# Velvet_Controller.net
KiCad netlist of a schematic drawn in Altium Designer
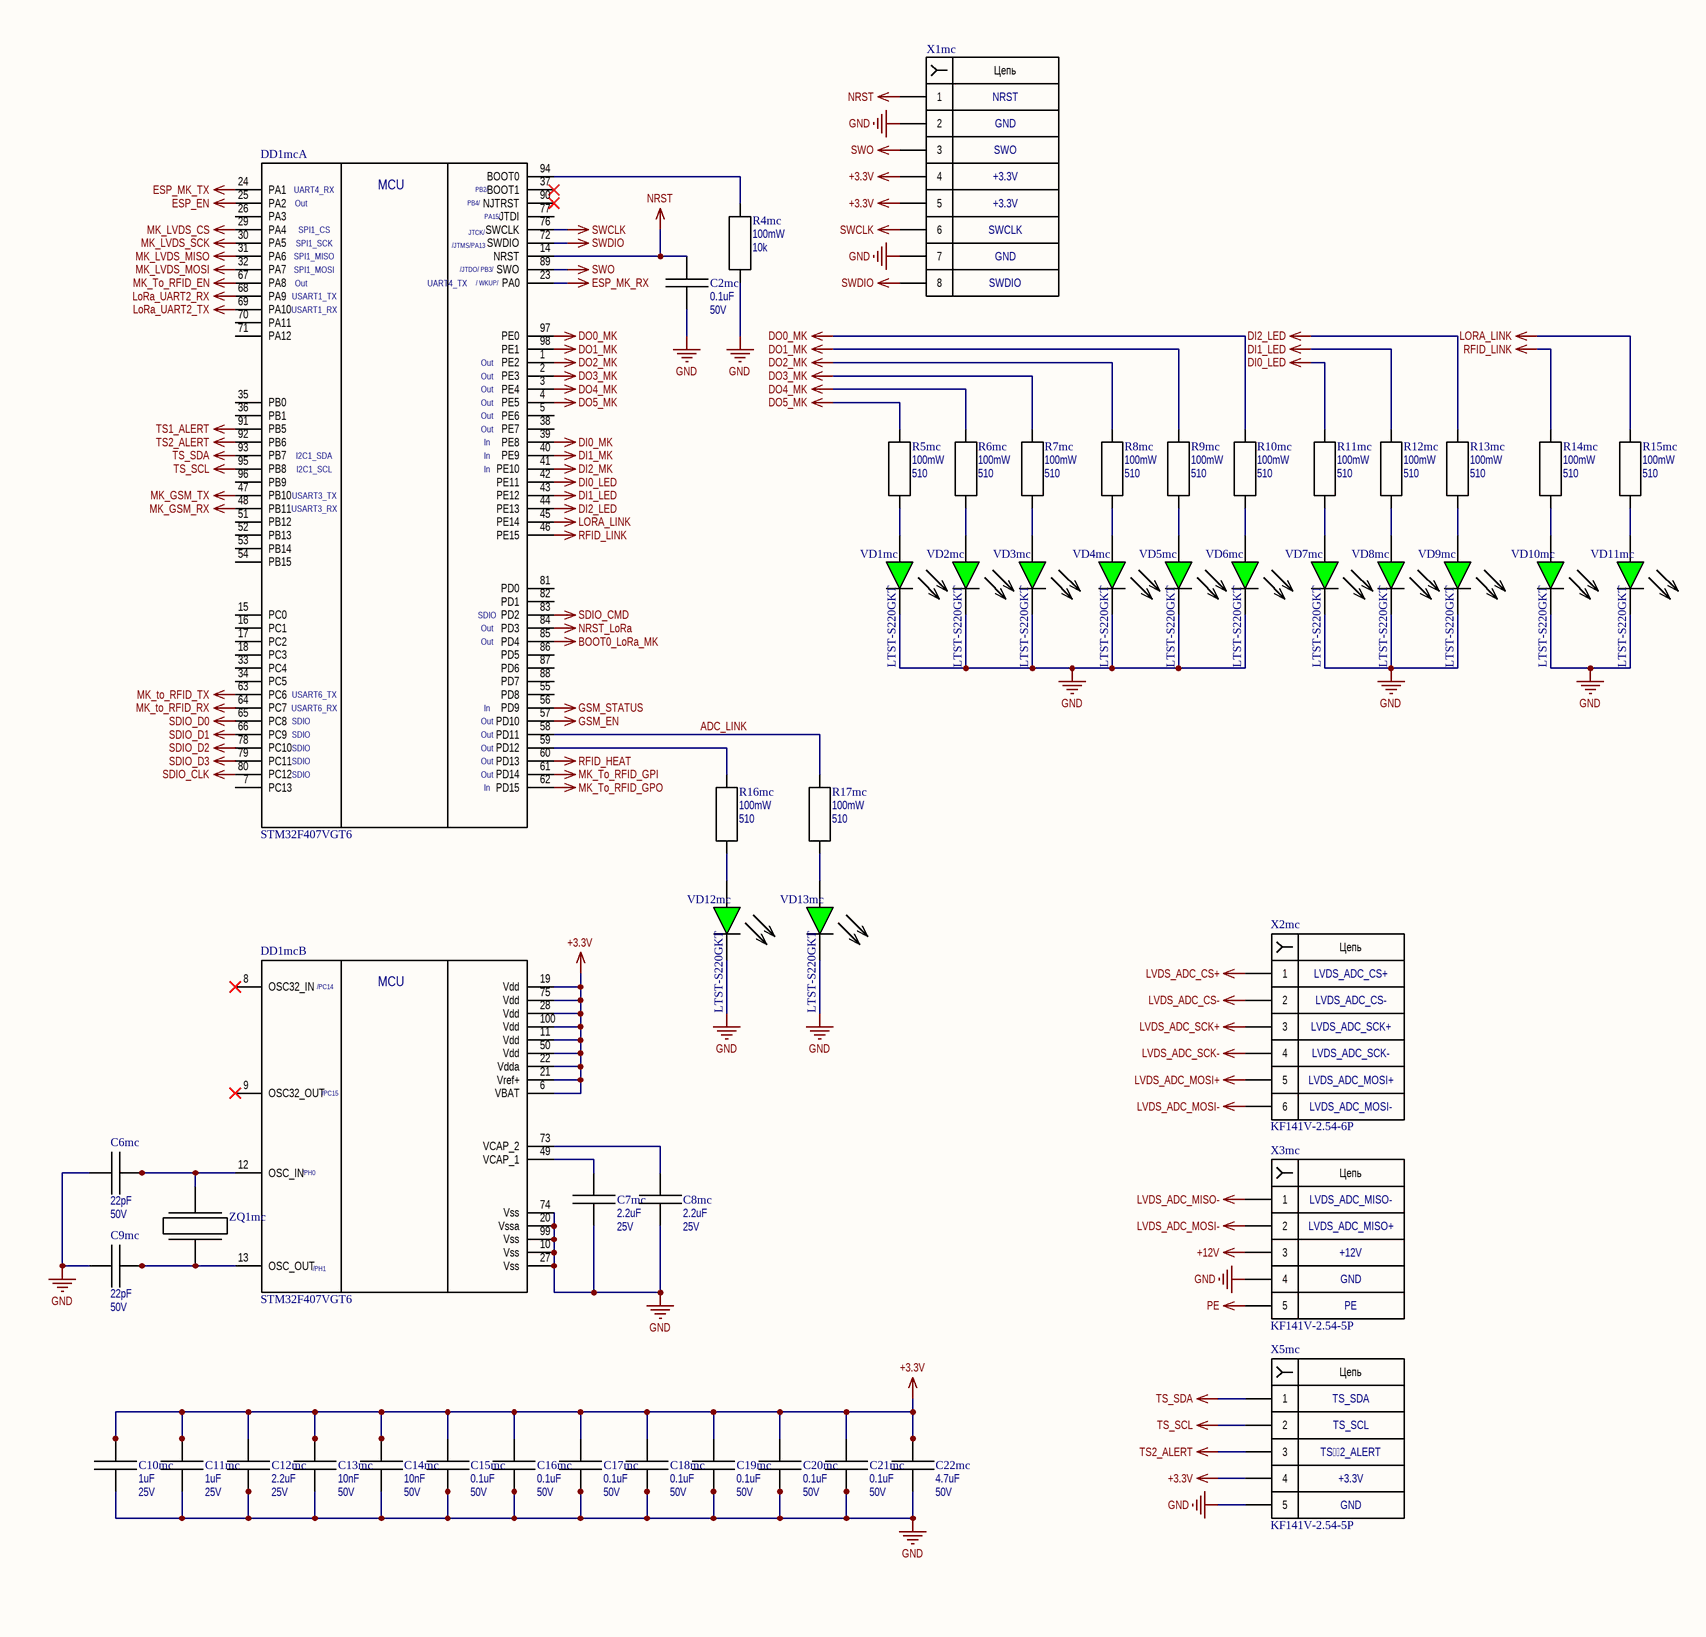
[diagram p0: Схема МК и датчиков Velvet Controller.SchDoc, left]
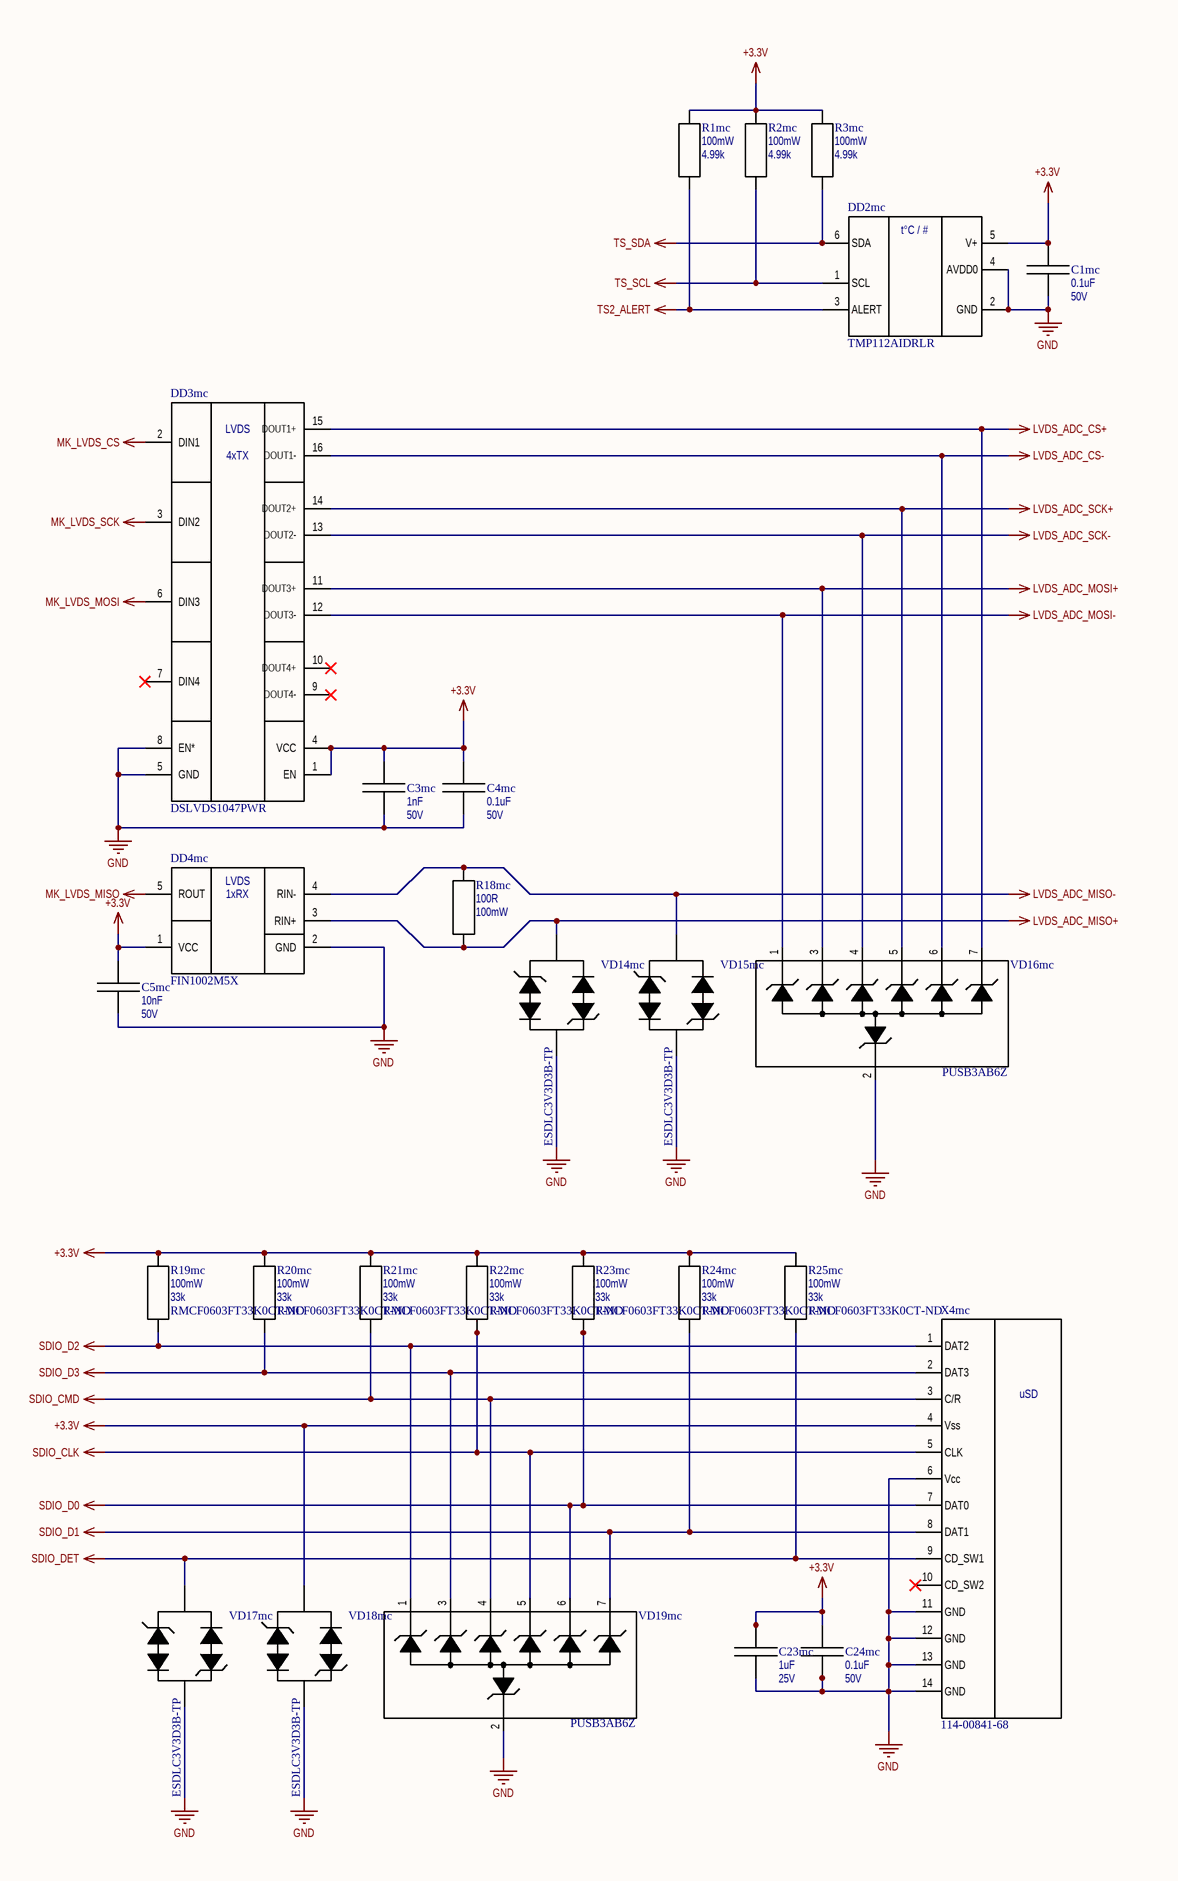
[diagram p1: Схема МК и датчиков Velvet Controller.SchDoc, right]

(export (version "E")
  (design (tool "Eeschema 10.0.6"))
  (components
    (comp (ref "C1mc")
      (value "GCM188R71H104KA57D")
      (footprint "CAP 0603 IPC MAX")
      (description "CAP SMD CER 0.1UF 50V X7R 0603")
      (fields
        (field (name "TOLERANCE") "10%")
        (field (name "CAPACITANCE") "0.1uF")
        (field (name "RATED VOLTAGE") "50V")
      )
      (libsource (lib "Passive components") (part "GCM188R71H104KA57D"))
    )
    (comp (ref "C2mc")
      (value "GCM188R71H104KA57D")
      (footprint "CAP 0603 IPC MAX")
      (description "CAP SMD CER 0.1UF 50V X7R 0603")
      (fields
        (field (name "TOLERANCE") "10%")
        (field (name "CAPACITANCE") "0.1uF")
        (field (name "RATED VOLTAGE") "50V")
      )
      (libsource (lib "Passive components") (part "GCM188R71H104KA57D"))
    )
    (comp (ref "C3mc")
      (value "GCM188R71H102KA37D")
      (footprint "CAP 0603 IPC MAX")
      (description "CAP SMD CER 1000PF 50V X7R 0603")
      (fields
        (field (name "TOLERANCE") "10%")
        (field (name "CAPACITANCE") "1nF")
        (field (name "RATED VOLTAGE") "50V")
      )
      (libsource (lib "Passive components") (part "GCM188R71H102KA37D"))
    )
    (comp (ref "C4mc")
      (value "GCM188R71H104KA57D")
      (footprint "CAP 0603 IPC MAX")
      (description "CAP SMD CER 0.1UF 50V X7R 0603")
      (fields
        (field (name "TOLERANCE") "10%")
        (field (name "CAPACITANCE") "0.1uF")
        (field (name "RATED VOLTAGE") "50V")
      )
      (libsource (lib "Passive components") (part "GCM188R71H104KA57D"))
    )
    (comp (ref "C5mc")
      (value "CL10B103KB8NNNC")
      (footprint "CAP 0603 IPC MAX")
      (description "CAP SMD CER 10000PF 50V X7R 0603")
      (fields
        (field (name "TOLERANCE") "10%")
        (field (name "CAPACITANCE") "10nF")
        (field (name "RATED VOLTAGE") "50V")
      )
      (libsource (lib "Passive components") (part "CL10B103KB8NNNC"))
    )
    (comp (ref "C6mc")
      (value "CC0603JRNPO9BN220")
      (footprint "CAP 0603 IPC MAX")
      (description "CAP SMD CER 22PF 50V NP0  0603")
      (fields
        (field (name "TOLERANCE") "5%")
        (field (name "CAPACITANCE") "22pF")
        (field (name "RATED VOLTAGE") "50V")
      )
      (libsource (lib "Passive components") (part "CC0603JRNPO9BN220"))
    )
    (comp (ref "C7mc")
      (value "GRM188R61E225KA12D")
      (footprint "CAP 0603 IPC MAX")
      (description "CAP SMD CER 2.2UF 25V X5R 0603")
      (fields
        (field (name "TOLERANCE") "10%")
        (field (name "CAPACITANCE") "2.2uF")
        (field (name "RATED VOLTAGE") "25V")
      )
      (libsource (lib "Passive components") (part "GRM188R61E225KA12D"))
    )
    (comp (ref "C8mc")
      (value "GRM188R61E225KA12D")
      (footprint "CAP 0603 IPC MAX")
      (description "CAP SMD CER 2.2UF 25V X5R 0603")
      (fields
        (field (name "TOLERANCE") "10%")
        (field (name "CAPACITANCE") "2.2uF")
        (field (name "RATED VOLTAGE") "25V")
      )
      (libsource (lib "Passive components") (part "GRM188R61E225KA12D"))
    )
    (comp (ref "C9mc")
      (value "CC0603JRNPO9BN220")
      (footprint "CAP 0603 IPC MAX")
      (description "CAP SMD CER 22PF 50V NP0  0603")
      (fields
        (field (name "TOLERANCE") "5%")
        (field (name "CAPACITANCE") "22pF")
        (field (name "RATED VOLTAGE") "50V")
      )
      (libsource (lib "Passive components") (part "CC0603JRNPO9BN220"))
    )
    (comp (ref "C10mc")
      (value "TMK107BJ105KA-T")
      (footprint "CAP 0603 IPC MAX")
      (description "CAP SMD CER 1UF 25V X5R 0603")
      (fields
        (field (name "TOLERANCE") "10%")
        (field (name "CAPACITANCE") "1uF")
        (field (name "RATED VOLTAGE") "25V")
      )
      (libsource (lib "Passive components") (part "TMK107BJ105KA-T"))
    )
    (comp (ref "C11mc")
      (value "TMK107BJ105KA-T")
      (footprint "CAP 0603 IPC MAX")
      (description "CAP SMD CER 1UF 25V X5R 0603")
      (fields
        (field (name "TOLERANCE") "10%")
        (field (name "CAPACITANCE") "1uF")
        (field (name "RATED VOLTAGE") "25V")
      )
      (libsource (lib "Passive components") (part "TMK107BJ105KA-T"))
    )
    (comp (ref "C12mc")
      (value "GRM188R61E225KA12D")
      (footprint "CAP 0603 IPC MAX")
      (description "CAP SMD CER 2.2UF 25V X5R 0603")
      (fields
        (field (name "TOLERANCE") "10%")
        (field (name "CAPACITANCE") "2.2uF")
        (field (name "RATED VOLTAGE") "25V")
      )
      (libsource (lib "Passive components") (part "GRM188R61E225KA12D"))
    )
    (comp (ref "C13mc")
      (value "CL10B103KB8NNNC")
      (footprint "CAP 0603 IPC MAX")
      (description "CAP SMD CER 10000PF 50V X7R 0603")
      (fields
        (field (name "TOLERANCE") "10%")
        (field (name "CAPACITANCE") "10nF")
        (field (name "RATED VOLTAGE") "50V")
      )
      (libsource (lib "Passive components") (part "CL10B103KB8NNNC"))
    )
    (comp (ref "C14mc")
      (value "CL10B103KB8NNNC")
      (footprint "CAP 0603 IPC MAX")
      (description "CAP SMD CER 10000PF 50V X7R 0603")
      (fields
        (field (name "TOLERANCE") "10%")
        (field (name "CAPACITANCE") "10nF")
        (field (name "RATED VOLTAGE") "50V")
      )
      (libsource (lib "Passive components") (part "CL10B103KB8NNNC"))
    )
    (comp (ref "C15mc")
      (value "GCM188R71H104KA57D")
      (footprint "CAP 0603 IPC MAX")
      (description "CAP SMD CER 0.1UF 50V X7R 0603")
      (fields
        (field (name "TOLERANCE") "10%")
        (field (name "CAPACITANCE") "0.1uF")
        (field (name "RATED VOLTAGE") "50V")
      )
      (libsource (lib "Passive components") (part "GCM188R71H104KA57D"))
    )
    (comp (ref "C16mc")
      (value "GCM188R71H104KA57D")
      (footprint "CAP 0603 IPC MAX")
      (description "CAP SMD CER 0.1UF 50V X7R 0603")
      (fields
        (field (name "TOLERANCE") "10%")
        (field (name "CAPACITANCE") "0.1uF")
        (field (name "RATED VOLTAGE") "50V")
      )
      (libsource (lib "Passive components") (part "GCM188R71H104KA57D"))
    )
    (comp (ref "C17mc")
      (value "GCM188R71H104KA57D")
      (footprint "CAP 0603 IPC MAX")
      (description "CAP SMD CER 0.1UF 50V X7R 0603")
      (fields
        (field (name "TOLERANCE") "10%")
        (field (name "CAPACITANCE") "0.1uF")
        (field (name "RATED VOLTAGE") "50V")
      )
      (libsource (lib "Passive components") (part "GCM188R71H104KA57D"))
    )
    (comp (ref "C18mc")
      (value "GCM188R71H104KA57D")
      (footprint "CAP 0603 IPC MAX")
      (description "CAP SMD CER 0.1UF 50V X7R 0603")
      (fields
        (field (name "TOLERANCE") "10%")
        (field (name "CAPACITANCE") "0.1uF")
        (field (name "RATED VOLTAGE") "50V")
      )
      (libsource (lib "Passive components") (part "GCM188R71H104KA57D"))
    )
    (comp (ref "C19mc")
      (value "GCM188R71H104KA57D")
      (footprint "CAP 0603 IPC MAX")
      (description "CAP SMD CER 0.1UF 50V X7R 0603")
      (fields
        (field (name "TOLERANCE") "10%")
        (field (name "CAPACITANCE") "0.1uF")
        (field (name "RATED VOLTAGE") "50V")
      )
      (libsource (lib "Passive components") (part "GCM188R71H104KA57D"))
    )
    (comp (ref "C20mc")
      (value "GCM188R71H104KA57D")
      (footprint "CAP 0603 IPC MAX")
      (description "CAP SMD CER 0.1UF 50V X7R 0603")
      (fields
        (field (name "TOLERANCE") "10%")
        (field (name "CAPACITANCE") "0.1uF")
        (field (name "RATED VOLTAGE") "50V")
      )
      (libsource (lib "Passive components") (part "GCM188R71H104KA57D"))
    )
    (comp (ref "C21mc")
      (value "GCM188R71H104KA57D")
      (footprint "CAP 0603 IPC MAX")
      (description "CAP SMD CER 0.1UF 50V X7R 0603")
      (fields
        (field (name "TOLERANCE") "10%")
        (field (name "CAPACITANCE") "0.1uF")
        (field (name "RATED VOLTAGE") "50V")
      )
      (libsource (lib "Passive components") (part "GCM188R71H104KA57D"))
    )
    (comp (ref "C22mc")
      (value "CL21A475KBQNNNE")
      (footprint "CAP 0805 IPC MAX")
      (description "CAP SMD CER 4.7UF 50V X5R 0805")
      (fields
        (field (name "TOLERANCE") "10%")
        (field (name "CAPACITANCE") "4.7uF")
        (field (name "RATED VOLTAGE") "50V")
      )
      (libsource (lib "Passive components") (part "CL21A475KBQNNNE"))
    )
    (comp (ref "C23mc")
      (value "TMK107BJ105KA-T")
      (footprint "CAP 0603 IPC MAX")
      (description "CAP SMD CER 1UF 25V X5R 0603")
      (fields
        (field (name "TOLERANCE") "10%")
        (field (name "CAPACITANCE") "1uF")
        (field (name "RATED VOLTAGE") "25V")
      )
      (libsource (lib "Passive components") (part "TMK107BJ105KA-T"))
    )
    (comp (ref "C24mc")
      (value "GCM188R71H104KA57D")
      (footprint "CAP 0603 IPC MAX")
      (description "CAP SMD CER 0.1UF 50V X7R 0603")
      (fields
        (field (name "TOLERANCE") "10%")
        (field (name "CAPACITANCE") "0.1uF")
        (field (name "RATED VOLTAGE") "50V")
      )
      (libsource (lib "Passive components") (part "GCM188R71H104KA57D"))
    )
    (comp (ref "DD1mc")
      (value "STM32F407VGT6")
      (footprint "LQFP50P1600X1600X160-100M")
      (description "IC MCU 32BIT 1MB FLASH 100LQFP")
      (libsource (lib "Digital") (part "STM32F407VGT6"))
    )
    (comp (ref "DD2mc")
      (value "TMP112AIDRLR")
      (footprint "SOT-563")
      (description "SOT-563 TEMPERATURE SENSORS ROHS")
      (libsource (lib "Digital") (part "TMP112AIDRLR"))
    )
    (comp (ref "DD3mc")
      (value "DSLVDS1047PWR")
      (footprint "TSSOP-16")
      (description "IC DRIVER LVDS FULL 4/0 16TSSOP")
      (libsource (lib "Digital") (part "DSLVDS1047PWR"))
    )
    (comp (ref "DD4mc")
      (value "FIN1002M5X")
      (footprint "SOT-23-5")
      (description "IC RECEIVER LVDS 0/1 SOT23-5")
      (libsource (lib "Digital") (part "FIN1002M5X"))
    )
    (comp (ref "R1mc")
      (value "RC0603FR-074K99L")
      (footprint "RES 0603 IPC MAX")
      (description "RES SMD 4.99K OHM 1% 1/10W 0603")
      (fields
        (field (name "TOLERANCE") "1%")
        (field (name "RATED POWER") "100mW")
        (field (name "RESISTANCE") "4.99k")
      )
      (libsource (lib "Passive components") (part "RC0603FR-074K99L"))
    )
    (comp (ref "R2mc")
      (value "RC0603FR-074K99L")
      (footprint "RES 0603 IPC MAX")
      (description "RES SMD 4.99K OHM 1% 1/10W 0603")
      (fields
        (field (name "TOLERANCE") "1%")
        (field (name "RATED POWER") "100mW")
        (field (name "RESISTANCE") "4.99k")
      )
      (libsource (lib "Passive components") (part "RC0603FR-074K99L"))
    )
    (comp (ref "R3mc")
      (value "RC0603FR-074K99L")
      (footprint "RES 0603 IPC MAX")
      (description "RES SMD 4.99K OHM 1% 1/10W 0603")
      (fields
        (field (name "TOLERANCE") "1%")
        (field (name "RATED POWER") "100mW")
        (field (name "RESISTANCE") "4.99k")
      )
      (libsource (lib "Passive components") (part "RC0603FR-074K99L"))
    )
    (comp (ref "R4mc")
      (value "RMCF0603JT10K0")
      (footprint "RES 0603 IPC MAX")
      (description "RES SMD 10K OHM 5% 1/10W 0603")
      (fields
        (field (name "TOLERANCE") "5%")
        (field (name "POWER RATED") "100mW")
        (field (name "RESISTANCE") "10k")
      )
      (libsource (lib "Passive components") (part "RMCF0603JT10K0"))
    )
    (comp (ref "R5mc")
      (value "RMCF0603JT510R")
      (footprint "RES 0603 IPC MAX")
      (description "RES SMD 510 OHM 5% 1/10W 0603")
      (fields
        (field (name "TOLERANCE") "5%")
        (field (name "POWER RATED") "100mW")
        (field (name "RESISTANCE") "510")
      )
      (libsource (lib "Passive components") (part "RMCF0603JT510R"))
    )
    (comp (ref "R6mc")
      (value "RMCF0603JT510R")
      (footprint "RES 0603 IPC MAX")
      (description "RES SMD 510 OHM 5% 1/10W 0603")
      (fields
        (field (name "TOLERANCE") "5%")
        (field (name "POWER RATED") "100mW")
        (field (name "RESISTANCE") "510")
      )
      (libsource (lib "Passive components") (part "RMCF0603JT510R"))
    )
    (comp (ref "R7mc")
      (value "RMCF0603JT510R")
      (footprint "RES 0603 IPC MAX")
      (description "RES SMD 510 OHM 5% 1/10W 0603")
      (fields
        (field (name "TOLERANCE") "5%")
        (field (name "POWER RATED") "100mW")
        (field (name "RESISTANCE") "510")
      )
      (libsource (lib "Passive components") (part "RMCF0603JT510R"))
    )
    (comp (ref "R8mc")
      (value "RMCF0603JT510R")
      (footprint "RES 0603 IPC MAX")
      (description "RES SMD 510 OHM 5% 1/10W 0603")
      (fields
        (field (name "TOLERANCE") "5%")
        (field (name "POWER RATED") "100mW")
        (field (name "RESISTANCE") "510")
      )
      (libsource (lib "Passive components") (part "RMCF0603JT510R"))
    )
    (comp (ref "R9mc")
      (value "RMCF0603JT510R")
      (footprint "RES 0603 IPC MAX")
      (description "RES SMD 510 OHM 5% 1/10W 0603")
      (fields
        (field (name "TOLERANCE") "5%")
        (field (name "POWER RATED") "100mW")
        (field (name "RESISTANCE") "510")
      )
      (libsource (lib "Passive components") (part "RMCF0603JT510R"))
    )
    (comp (ref "R10mc")
      (value "RMCF0603JT510R")
      (footprint "RES 0603 IPC MAX")
      (description "RES SMD 510 OHM 5% 1/10W 0603")
      (fields
        (field (name "TOLERANCE") "5%")
        (field (name "POWER RATED") "100mW")
        (field (name "RESISTANCE") "510")
      )
      (libsource (lib "Passive components") (part "RMCF0603JT510R"))
    )
    (comp (ref "R11mc")
      (value "RMCF0603JT510R")
      (footprint "RES 0603 IPC MAX")
      (description "RES SMD 510 OHM 5% 1/10W 0603")
      (fields
        (field (name "TOLERANCE") "5%")
        (field (name "POWER RATED") "100mW")
        (field (name "RESISTANCE") "510")
      )
      (libsource (lib "Passive components") (part "RMCF0603JT510R"))
    )
    (comp (ref "R12mc")
      (value "RMCF0603JT510R")
      (footprint "RES 0603 IPC MAX")
      (description "RES SMD 510 OHM 5% 1/10W 0603")
      (fields
        (field (name "TOLERANCE") "5%")
        (field (name "POWER RATED") "100mW")
        (field (name "RESISTANCE") "510")
      )
      (libsource (lib "Passive components") (part "RMCF0603JT510R"))
    )
    (comp (ref "R13mc")
      (value "RMCF0603JT510R")
      (footprint "RES 0603 IPC MAX")
      (description "RES SMD 510 OHM 5% 1/10W 0603")
      (fields
        (field (name "TOLERANCE") "5%")
        (field (name "POWER RATED") "100mW")
        (field (name "RESISTANCE") "510")
      )
      (libsource (lib "Passive components") (part "RMCF0603JT510R"))
    )
    (comp (ref "R14mc")
      (value "RMCF0603JT510R")
      (footprint "RES 0603 IPC MAX")
      (description "RES SMD 510 OHM 5% 1/10W 0603")
      (fields
        (field (name "TOLERANCE") "5%")
        (field (name "POWER RATED") "100mW")
        (field (name "RESISTANCE") "510")
      )
      (libsource (lib "Passive components") (part "RMCF0603JT510R"))
    )
    (comp (ref "R15mc")
      (value "RMCF0603JT510R")
      (footprint "RES 0603 IPC MAX")
      (description "RES SMD 510 OHM 5% 1/10W 0603")
      (fields
        (field (name "TOLERANCE") "5%")
        (field (name "POWER RATED") "100mW")
        (field (name "RESISTANCE") "510")
      )
      (libsource (lib "Passive components") (part "RMCF0603JT510R"))
    )
    (comp (ref "R16mc")
      (value "RMCF0603JT510R")
      (footprint "RES 0603 IPC MAX")
      (description "RES SMD 510 OHM 5% 1/10W 0603")
      (fields
        (field (name "TOLERANCE") "5%")
        (field (name "POWER RATED") "100mW")
        (field (name "RESISTANCE") "510")
      )
      (libsource (lib "Passive components") (part "RMCF0603JT510R"))
    )
    (comp (ref "R17mc")
      (value "RMCF0603JT510R")
      (footprint "RES 0603 IPC MAX")
      (description "RES SMD 510 OHM 5% 1/10W 0603")
      (fields
        (field (name "TOLERANCE") "5%")
        (field (name "POWER RATED") "100mW")
        (field (name "RESISTANCE") "510")
      )
      (libsource (lib "Passive components") (part "RMCF0603JT510R"))
    )
    (comp (ref "R18mc")
      (value "RMCF0603FT100R")
      (footprint "RES 0603 IPC MAX")
      (description "RES SMD 100 OHM 1% 1/10W 0603")
      (fields
        (field (name "TOLERANCE") "1%")
        (field (name "RESISTANCE") "100R")
        (field (name "RATED POWER") "100mW")
      )
      (libsource (lib "Passive components") (part "RMCF0603FT100R"))
    )
    (comp (ref "R19mc")
      (value "RMCF0603FT33K0")
      (footprint "RES 0603 IPC MAX")
      (description "RES SMD 33K OHM 1% 1/10W 0603")
      (fields
        (field (name "TOLERANCE") "1%")
        (field (name "POWER RATED") "100mW")
        (field (name "RESISTANCE") "33k")
        (field (name "SUPPLIER PART NUMBER 1") "RMCF0603FT33K0CT-ND")
      )
      (libsource (lib "Passive components") (part "RMCF0603FT33K0"))
    )
    (comp (ref "R20mc")
      (value "RMCF0603FT33K0")
      (footprint "RES 0603 IPC MAX")
      (description "RES SMD 33K OHM 1% 1/10W 0603")
      (fields
        (field (name "TOLERANCE") "1%")
        (field (name "POWER RATED") "100mW")
        (field (name "RESISTANCE") "33k")
        (field (name "SUPPLIER PART NUMBER 1") "RMCF0603FT33K0CT-ND")
      )
      (libsource (lib "Passive components") (part "RMCF0603FT33K0"))
    )
    (comp (ref "R21mc")
      (value "RMCF0603FT33K0")
      (footprint "RES 0603 IPC MAX")
      (description "RES SMD 33K OHM 1% 1/10W 0603")
      (fields
        (field (name "TOLERANCE") "1%")
        (field (name "POWER RATED") "100mW")
        (field (name "RESISTANCE") "33k")
        (field (name "SUPPLIER PART NUMBER 1") "RMCF0603FT33K0CT-ND")
      )
      (libsource (lib "Passive components") (part "RMCF0603FT33K0"))
    )
    (comp (ref "R22mc")
      (value "RMCF0603FT33K0")
      (footprint "RES 0603 IPC MAX")
      (description "RES SMD 33K OHM 1% 1/10W 0603")
      (fields
        (field (name "TOLERANCE") "1%")
        (field (name "POWER RATED") "100mW")
        (field (name "RESISTANCE") "33k")
        (field (name "SUPPLIER PART NUMBER 1") "RMCF0603FT33K0CT-ND")
      )
      (libsource (lib "Passive components") (part "RMCF0603FT33K0"))
    )
    (comp (ref "R23mc")
      (value "RMCF0603FT33K0")
      (footprint "RES 0603 IPC MAX")
      (description "RES SMD 33K OHM 1% 1/10W 0603")
      (fields
        (field (name "TOLERANCE") "1%")
        (field (name "POWER RATED") "100mW")
        (field (name "RESISTANCE") "33k")
        (field (name "SUPPLIER PART NUMBER 1") "RMCF0603FT33K0CT-ND")
      )
      (libsource (lib "Passive components") (part "RMCF0603FT33K0"))
    )
    (comp (ref "R24mc")
      (value "RMCF0603FT33K0")
      (footprint "RES 0603 IPC MAX")
      (description "RES SMD 33K OHM 1% 1/10W 0603")
      (fields
        (field (name "TOLERANCE") "1%")
        (field (name "POWER RATED") "100mW")
        (field (name "RESISTANCE") "33k")
        (field (name "SUPPLIER PART NUMBER 1") "RMCF0603FT33K0CT-ND")
      )
      (libsource (lib "Passive components") (part "RMCF0603FT33K0"))
    )
    (comp (ref "R25mc")
      (value "RMCF0603FT33K0")
      (footprint "RES 0603 IPC MAX")
      (description "RES SMD 33K OHM 1% 1/10W 0603")
      (fields
        (field (name "TOLERANCE") "1%")
        (field (name "POWER RATED") "100mW")
        (field (name "RESISTANCE") "33k")
        (field (name "SUPPLIER PART NUMBER 1") "RMCF0603FT33K0CT-ND")
      )
      (libsource (lib "Passive components") (part "RMCF0603FT33K0"))
    )
    (comp (ref "VD1mc")
      (value "LTST-S220GKT")
      (footprint "0805 DIODE")
      (description "LED GREEN CLEAR SMD R/A")
      (libsource (lib "Diodes") (part "LTST-S220GKT"))
    )
    (comp (ref "VD2mc")
      (value "LTST-S220GKT")
      (footprint "0805 DIODE")
      (description "LED GREEN CLEAR SMD R/A")
      (libsource (lib "Diodes") (part "LTST-S220GKT"))
    )
    (comp (ref "VD3mc")
      (value "LTST-S220GKT")
      (footprint "0805 DIODE")
      (description "LED GREEN CLEAR SMD R/A")
      (libsource (lib "Diodes") (part "LTST-S220GKT"))
    )
    (comp (ref "VD4mc")
      (value "LTST-S220GKT")
      (footprint "0805 DIODE")
      (description "LED GREEN CLEAR SMD R/A")
      (libsource (lib "Diodes") (part "LTST-S220GKT"))
    )
    (comp (ref "VD5mc")
      (value "LTST-S220GKT")
      (footprint "0805 DIODE")
      (description "LED GREEN CLEAR SMD R/A")
      (libsource (lib "Diodes") (part "LTST-S220GKT"))
    )
    (comp (ref "VD6mc")
      (value "LTST-S220GKT")
      (footprint "0805 DIODE")
      (description "LED GREEN CLEAR SMD R/A")
      (libsource (lib "Diodes") (part "LTST-S220GKT"))
    )
    (comp (ref "VD7mc")
      (value "LTST-S220GKT")
      (footprint "0805 DIODE")
      (description "LED GREEN CLEAR SMD R/A")
      (libsource (lib "Diodes") (part "LTST-S220GKT"))
    )
    (comp (ref "VD8mc")
      (value "LTST-S220GKT")
      (footprint "0805 DIODE")
      (description "LED GREEN CLEAR SMD R/A")
      (libsource (lib "Diodes") (part "LTST-S220GKT"))
    )
    (comp (ref "VD9mc")
      (value "LTST-S220GKT")
      (footprint "0805 DIODE")
      (description "LED GREEN CLEAR SMD R/A")
      (libsource (lib "Diodes") (part "LTST-S220GKT"))
    )
    (comp (ref "VD10mc")
      (value "LTST-S220GKT")
      (footprint "0805 DIODE")
      (description "LED GREEN CLEAR SMD R/A")
      (libsource (lib "Diodes") (part "LTST-S220GKT"))
    )
    (comp (ref "VD11mc")
      (value "LTST-S220GKT")
      (footprint "0805 DIODE")
      (description "LED GREEN CLEAR SMD R/A")
      (libsource (lib "Diodes") (part "LTST-S220GKT"))
    )
    (comp (ref "VD12mc")
      (value "LTST-S220GKT")
      (footprint "0805 DIODE")
      (description "LED GREEN CLEAR SMD R/A")
      (libsource (lib "Diodes") (part "LTST-S220GKT"))
    )
    (comp (ref "VD13mc")
      (value "LTST-S220GKT")
      (footprint "0805 DIODE")
      (description "LED GREEN CLEAR SMD R/A")
      (libsource (lib "Diodes") (part "LTST-S220GKT"))
    )
    (comp (ref "VD14mc")
      (value "ESDLC3V3D3B-TP")
      (footprint "SOD-323 (UNMARKED)")
      (description "TVS DIODE 3.3VWM 36VC SOD323")
      (libsource (lib "Diodes") (part "ESDLC3V3D3B-TP"))
    )
    (comp (ref "VD15mc")
      (value "ESDLC3V3D3B-TP")
      (footprint "SOD-323 (UNMARKED)")
      (description "TVS DIODE 3.3VWM 36VC SOD323")
      (libsource (lib "Diodes") (part "ESDLC3V3D3B-TP"))
    )
    (comp (ref "VD16mc")
      (value "PUSB3AB6Z")
      (footprint "DFN2111-7 (SOT1358-1)")
      (description "TVS DIODE 3.3VWM 6VC 7XSON")
      (libsource (lib "Diodes") (part "PUSB3AB6Z"))
    )
    (comp (ref "VD17mc")
      (value "ESDLC3V3D3B-TP")
      (footprint "SOD-323 (UNMARKED)")
      (description "TVS DIODE 3.3VWM 36VC SOD323")
      (libsource (lib "Diodes") (part "ESDLC3V3D3B-TP"))
    )
    (comp (ref "VD18mc")
      (value "ESDLC3V3D3B-TP")
      (footprint "SOD-323 (UNMARKED)")
      (description "TVS DIODE 3.3VWM 36VC SOD323")
      (libsource (lib "Diodes") (part "ESDLC3V3D3B-TP"))
    )
    (comp (ref "VD19mc")
      (value "PUSB3AB6Z")
      (footprint "DFN2111-7 (SOT1358-1)")
      (description "TVS DIODE 3.3VWM 6VC 7XSON")
      (libsource (lib "Diodes") (part "PUSB3AB6Z"))
    )
    (comp (ref "X1mc")
      (value "TSW-104-07-F-D")
      (footprint "HEADER 2.54mm 2ROW 8PIN")
      (description "CONN HEADER VERT 8POS 2.54MM 2ROWx4")
      (libsource (lib "Connectors") (part "TSW-104-07-F-D"))
    )
    (comp (ref "X2mc")
      (value "KF141V-2.54-6P")
      (footprint "KF141V-2.54-6P")
      (description "TERMINAL BLOCK 6 PIN 2.54mm 2A 150V T/H")
      (libsource (lib "Connectors") (part "KF141V-2.54-6P"))
    )
    (comp (ref "X3mc")
      (value "KF141V-2.54-5P")
      (footprint "KF141V-2.54-5P")
      (description "TERMINAL BLOCK 5 PIN 2.54mm 2A 150V T/H")
      (libsource (lib "Connectors") (part "KF141V-2.54-5P"))
    )
    (comp (ref "X4mc")
      (value "114-00841-68")
      (footprint "114-00841-68")
      (description "CONN MICRO SD CARD PUSH-PULL R/A")
      (libsource (lib "Connectors") (part "114-00841-68"))
    )
    (comp (ref "X5mc")
      (value "KF141V-2.54-5P")
      (footprint "KF141V-2.54-5P")
      (description "TERMINAL BLOCK 5 PIN 2.54mm 2A 150V T/H")
      (libsource (lib "Connectors") (part "KF141V-2.54-5P"))
    )
    (comp (ref "ZQ1mc")
      (value "ABM3-8.000MHZ-D2Y-T")
      (footprint "ABM3-8.000MHZ-D2Y-T")
      (description "CRYSTAL 8.0000MHZ 18PF SMD")
      (libsource (lib "Passive components") (part "ABM3-8.000MHZ-D2Y-T"))
    )
  )
  (nets
    (net (code "1") (name "+3.3V") (class "Default")
      (node (ref "C10mc") (pin "1") (pinfunction "1_1") (pintype "passive"))
      (node (ref "C11mc") (pin "1") (pinfunction "1_1") (pintype "passive"))
      (node (ref "C12mc") (pin "1") (pinfunction "1_1") (pintype "passive"))
      (node (ref "C13mc") (pin "1") (pinfunction "1_1") (pintype "passive"))
      (node (ref "C14mc") (pin "1") (pinfunction "1_1") (pintype "passive"))
      (node (ref "C15mc") (pin "1") (pinfunction "1_1") (pintype "passive"))
      (node (ref "C16mc") (pin "1") (pinfunction "1_1") (pintype "passive"))
      (node (ref "C17mc") (pin "1") (pinfunction "1_1") (pintype "passive"))
      (node (ref "C18mc") (pin "1") (pinfunction "1_1") (pintype "passive"))
      (node (ref "C19mc") (pin "1") (pinfunction "1_1") (pintype "passive"))
      (node (ref "C1mc") (pin "1") (pinfunction "1_1") (pintype "passive"))
      (node (ref "C20mc") (pin "1") (pinfunction "1_1") (pintype "passive"))
      (node (ref "C21mc") (pin "1") (pinfunction "1_1") (pintype "passive"))
      (node (ref "C22mc") (pin "1") (pinfunction "1_1") (pintype "passive"))
      (node (ref "C23mc") (pin "2") (pinfunction "2_2") (pintype "passive"))
      (node (ref "C24mc") (pin "1") (pinfunction "1_1") (pintype "passive"))
      (node (ref "C3mc") (pin "1") (pinfunction "1_1") (pintype "passive"))
      (node (ref "C4mc") (pin "1") (pinfunction "1_1") (pintype "passive"))
      (node (ref "C5mc") (pin "1") (pinfunction "1_1") (pintype "passive"))
      (node (ref "DD1mc") (pin "100") (pinfunction "Vdd_100") (pintype "passive"))
      (node (ref "DD1mc") (pin "11") (pinfunction "Vdd_11") (pintype "passive"))
      (node (ref "DD1mc") (pin "19") (pinfunction "Vdd_19") (pintype "passive"))
      (node (ref "DD1mc") (pin "21") (pinfunction "Vref+_21") (pintype "passive"))
      (node (ref "DD1mc") (pin "22") (pinfunction "Vdda_22") (pintype "passive"))
      (node (ref "DD1mc") (pin "28") (pinfunction "Vdd_28") (pintype "passive"))
      (node (ref "DD1mc") (pin "50") (pinfunction "Vdd_50") (pintype "passive"))
      (node (ref "DD1mc") (pin "6") (pinfunction "VBAT_6") (pintype "passive"))
      (node (ref "DD1mc") (pin "75") (pinfunction "Vdd_75") (pintype "passive"))
      (node (ref "DD2mc") (pin "5") (pinfunction "V+_5") (pintype "passive"))
      (node (ref "DD3mc") (pin "1") (pinfunction "EN_1") (pintype "passive"))
      (node (ref "DD3mc") (pin "4") (pinfunction "VCC_4") (pintype "passive"))
      (node (ref "DD4mc") (pin "1") (pinfunction "VCC_1") (pintype "passive"))
      (node (ref "R19mc") (pin "2") (pinfunction "2_2") (pintype "passive"))
      (node (ref "R1mc") (pin "2") (pinfunction "2_2") (pintype "passive"))
      (node (ref "R20mc") (pin "1") (pinfunction "1_1") (pintype "passive"))
      (node (ref "R21mc") (pin "1") (pinfunction "1_1") (pintype "passive"))
      (node (ref "R22mc") (pin "1") (pinfunction "1_1") (pintype "passive"))
      (node (ref "R23mc") (pin "1") (pinfunction "1_1") (pintype "passive"))
      (node (ref "R24mc") (pin "1") (pinfunction "1_1") (pintype "passive"))
      (node (ref "R25mc") (pin "1") (pinfunction "1_1") (pintype "passive"))
      (node (ref "R2mc") (pin "2") (pinfunction "2_2") (pintype "passive"))
      (node (ref "R3mc") (pin "2") (pinfunction "2_2") (pintype "passive"))
      (node (ref "VD18mc") (pin "2") (pinfunction "2_2") (pintype "passive"))
      (node (ref "X1mc") (pin "4") (pinfunction "4_4") (pintype "passive"))
      (node (ref "X1mc") (pin "5") (pinfunction "5_5") (pintype "passive"))
      (node (ref "X4mc") (pin "4") (pinfunction "Vss_4") (pintype "passive"))
      (node (ref "X5mc") (pin "4") (pinfunction "4_4") (pintype "passive"))
    )
    (net (code "2") (name "+12V") (class "Default")
      (node (ref "X3mc") (pin "3") (pinfunction "3_3") (pintype "passive"))
    )
    (net (code "3") (name "/ADC_LINK") (class "Default")
      (node (ref "DD1mc") (pin "58") (pinfunction "PD11_58") (pintype "passive"))
      (node (ref "R17mc") (pin "2") (pinfunction "2_2") (pintype "passive"))
    )
    (net (code "4") (name "BOOT0_LoRa_MK") (class "Default")
      (node (ref "DD1mc") (pin "85") (pinfunction "PD4_85") (pintype "passive"))
    )
    (net (code "5") (name "DI0_LED") (class "Default")
      (node (ref "DD1mc") (pin "42") (pinfunction "PE11_42") (pintype "passive"))
      (node (ref "R11mc") (pin "2") (pinfunction "2_2") (pintype "passive"))
    )
    (net (code "6") (name "DI0_MK") (class "Default")
      (node (ref "DD1mc") (pin "39") (pinfunction "PE8_39") (pintype "passive"))
    )
    (net (code "7") (name "DI1_LED") (class "Default")
      (node (ref "DD1mc") (pin "43") (pinfunction "PE12_43") (pintype "passive"))
      (node (ref "R12mc") (pin "2") (pinfunction "2_2") (pintype "passive"))
    )
    (net (code "8") (name "DI1_MK") (class "Default")
      (node (ref "DD1mc") (pin "40") (pinfunction "PE9_40") (pintype "passive"))
    )
    (net (code "9") (name "DI2_LED") (class "Default")
      (node (ref "DD1mc") (pin "44") (pinfunction "PE13_44") (pintype "passive"))
      (node (ref "R13mc") (pin "2") (pinfunction "2_2") (pintype "passive"))
    )
    (net (code "10") (name "DI2_MK") (class "Default")
      (node (ref "DD1mc") (pin "41") (pinfunction "PE10_41") (pintype "passive"))
    )
    (net (code "11") (name "DO0_MK") (class "Default")
      (node (ref "DD1mc") (pin "97") (pinfunction "PE0_97") (pintype "passive"))
      (node (ref "R10mc") (pin "2") (pinfunction "2_2") (pintype "passive"))
    )
    (net (code "12") (name "DO1_MK") (class "Default")
      (node (ref "DD1mc") (pin "98") (pinfunction "PE1_98") (pintype "passive"))
      (node (ref "R9mc") (pin "2") (pinfunction "2_2") (pintype "passive"))
    )
    (net (code "13") (name "DO2_MK") (class "Default")
      (node (ref "DD1mc") (pin "1") (pinfunction "PE2_1") (pintype "passive"))
      (node (ref "R8mc") (pin "2") (pinfunction "2_2") (pintype "passive"))
    )
    (net (code "14") (name "DO3_MK") (class "Default")
      (node (ref "DD1mc") (pin "2") (pinfunction "PE3_2") (pintype "passive"))
      (node (ref "R7mc") (pin "2") (pinfunction "2_2") (pintype "passive"))
    )
    (net (code "15") (name "DO4_MK") (class "Default")
      (node (ref "DD1mc") (pin "3") (pinfunction "PE4_3") (pintype "passive"))
      (node (ref "R6mc") (pin "2") (pinfunction "2_2") (pintype "passive"))
    )
    (net (code "16") (name "DO5_MK") (class "Default")
      (node (ref "DD1mc") (pin "4") (pinfunction "PE5_4") (pintype "passive"))
      (node (ref "R5mc") (pin "2") (pinfunction "2_2") (pintype "passive"))
    )
    (net (code "17") (name "ESP_EN") (class "Default")
      (node (ref "DD1mc") (pin "25") (pinfunction "PA2_25") (pintype "passive"))
    )
    (net (code "18") (name "ESP_MK_RX") (class "Default")
      (node (ref "DD1mc") (pin "23") (pinfunction "PA0_23") (pintype "passive"))
    )
    (net (code "19") (name "ESP_MK_TX") (class "Default")
      (node (ref "DD1mc") (pin "24") (pinfunction "PA1_24") (pintype "passive"))
    )
    (net (code "20") (name "GND") (class "Default")
      (node (ref "C10mc") (pin "2") (pinfunction "2_2") (pintype "passive"))
      (node (ref "C11mc") (pin "2") (pinfunction "2_2") (pintype "passive"))
      (node (ref "C12mc") (pin "2") (pinfunction "2_2") (pintype "passive"))
      (node (ref "C13mc") (pin "2") (pinfunction "2_2") (pintype "passive"))
      (node (ref "C14mc") (pin "2") (pinfunction "2_2") (pintype "passive"))
      (node (ref "C15mc") (pin "2") (pinfunction "2_2") (pintype "passive"))
      (node (ref "C16mc") (pin "2") (pinfunction "2_2") (pintype "passive"))
      (node (ref "C17mc") (pin "2") (pinfunction "2_2") (pintype "passive"))
      (node (ref "C18mc") (pin "2") (pinfunction "2_2") (pintype "passive"))
      (node (ref "C19mc") (pin "2") (pinfunction "2_2") (pintype "passive"))
      (node (ref "C1mc") (pin "2") (pinfunction "2_2") (pintype "passive"))
      (node (ref "C20mc") (pin "2") (pinfunction "2_2") (pintype "passive"))
      (node (ref "C21mc") (pin "2") (pinfunction "2_2") (pintype "passive"))
      (node (ref "C22mc") (pin "2") (pinfunction "2_2") (pintype "passive"))
      (node (ref "C23mc") (pin "1") (pinfunction "1_1") (pintype "passive"))
      (node (ref "C24mc") (pin "2") (pinfunction "2_2") (pintype "passive"))
      (node (ref "C2mc") (pin "2") (pinfunction "2_2") (pintype "passive"))
      (node (ref "C3mc") (pin "2") (pinfunction "2_2") (pintype "passive"))
      (node (ref "C4mc") (pin "2") (pinfunction "2_2") (pintype "passive"))
      (node (ref "C5mc") (pin "2") (pinfunction "2_2") (pintype "passive"))
      (node (ref "C6mc") (pin "1") (pinfunction "1_1") (pintype "passive"))
      (node (ref "C7mc") (pin "2") (pinfunction "2_2") (pintype "passive"))
      (node (ref "C8mc") (pin "2") (pinfunction "2_2") (pintype "passive"))
      (node (ref "C9mc") (pin "1") (pinfunction "1_1") (pintype "passive"))
      (node (ref "DD1mc") (pin "10") (pinfunction "Vss_10") (pintype "passive"))
      (node (ref "DD1mc") (pin "20") (pinfunction "Vssa_20") (pintype "passive"))
      (node (ref "DD1mc") (pin "27") (pinfunction "Vss_27") (pintype "passive"))
      (node (ref "DD1mc") (pin "74") (pinfunction "Vss_74") (pintype "passive"))
      (node (ref "DD1mc") (pin "99") (pinfunction "Vss_99") (pintype "passive"))
      (node (ref "DD2mc") (pin "2") (pinfunction "GND_2") (pintype "passive"))
      (node (ref "DD2mc") (pin "4") (pinfunction "AVDD0_4") (pintype "passive"))
      (node (ref "DD3mc") (pin "5") (pinfunction "GND_5") (pintype "passive"))
      (node (ref "DD3mc") (pin "8") (pinfunction "EN*_8") (pintype "passive"))
      (node (ref "DD4mc") (pin "2") (pinfunction "GND_2") (pintype "passive"))
      (node (ref "R4mc") (pin "1") (pinfunction "1_1") (pintype "passive"))
      (node (ref "VD10mc") (pin "2") (pinfunction "2_2") (pintype "passive"))
      (node (ref "VD11mc") (pin "2") (pinfunction "2_2") (pintype "passive"))
      (node (ref "VD12mc") (pin "2") (pinfunction "2_2") (pintype "passive"))
      (node (ref "VD13mc") (pin "2") (pinfunction "2_2") (pintype "passive"))
      (node (ref "VD14mc") (pin "1") (pinfunction "1_1") (pintype "passive"))
      (node (ref "VD15mc") (pin "1") (pinfunction "1_1") (pintype "passive"))
      (node (ref "VD16mc") (pin "2") (pinfunction "2_2") (pintype "passive"))
      (node (ref "VD17mc") (pin "1") (pinfunction "1_1") (pintype "passive"))
      (node (ref "VD18mc") (pin "1") (pinfunction "1_1") (pintype "passive"))
      (node (ref "VD19mc") (pin "2") (pinfunction "2_2") (pintype "passive"))
      (node (ref "VD1mc") (pin "2") (pinfunction "2_2") (pintype "passive"))
      (node (ref "VD2mc") (pin "2") (pinfunction "2_2") (pintype "passive"))
      (node (ref "VD3mc") (pin "2") (pinfunction "2_2") (pintype "passive"))
      (node (ref "VD4mc") (pin "2") (pinfunction "2_2") (pintype "passive"))
      (node (ref "VD5mc") (pin "2") (pinfunction "2_2") (pintype "passive"))
      (node (ref "VD6mc") (pin "2") (pinfunction "2_2") (pintype "passive"))
      (node (ref "VD7mc") (pin "2") (pinfunction "2_2") (pintype "passive"))
      (node (ref "VD8mc") (pin "2") (pinfunction "2_2") (pintype "passive"))
      (node (ref "VD9mc") (pin "2") (pinfunction "2_2") (pintype "passive"))
      (node (ref "X1mc") (pin "2") (pinfunction "2_2") (pintype "passive"))
      (node (ref "X1mc") (pin "7") (pinfunction "7_7") (pintype "passive"))
      (node (ref "X3mc") (pin "4") (pinfunction "4_4") (pintype "passive"))
      (node (ref "X4mc") (pin "11") (pinfunction "GND_11") (pintype "passive"))
      (node (ref "X4mc") (pin "12") (pinfunction "GND_12") (pintype "passive"))
      (node (ref "X4mc") (pin "13") (pinfunction "GND_13") (pintype "passive"))
      (node (ref "X4mc") (pin "14") (pinfunction "GND_14") (pintype "passive"))
      (node (ref "X4mc") (pin "6") (pinfunction "Vcc_6") (pintype "passive"))
      (node (ref "X5mc") (pin "5") (pinfunction "5_5") (pintype "passive"))
    )
    (net (code "21") (name "GSM_EN") (class "Default")
      (node (ref "DD1mc") (pin "57") (pinfunction "PD10_57") (pintype "passive"))
    )
    (net (code "22") (name "GSM_STATUS") (class "Default")
      (node (ref "DD1mc") (pin "56") (pinfunction "PD9_56") (pintype "passive"))
    )
    (net (code "23") (name "LORA_LINK") (class "Default")
      (node (ref "DD1mc") (pin "45") (pinfunction "PE14_45") (pintype "passive"))
      (node (ref "R15mc") (pin "2") (pinfunction "2_2") (pintype "passive"))
    )
    (net (code "24") (name "LVDS_ADC_CS+") (class "Default")
      (node (ref "DD3mc") (pin "15") (pinfunction "DOUT1+_15") (pintype "passive"))
      (node (ref "VD16mc") (pin "7") (pinfunction "7_7") (pintype "passive"))
      (node (ref "X2mc") (pin "1") (pinfunction "1_1") (pintype "passive"))
    )
    (net (code "25") (name "LVDS_ADC_CS-") (class "Default")
      (node (ref "DD3mc") (pin "16") (pinfunction "DOUT1-_16") (pintype "passive"))
      (node (ref "VD16mc") (pin "6") (pinfunction "6_6") (pintype "passive"))
      (node (ref "X2mc") (pin "2") (pinfunction "2_2") (pintype "passive"))
    )
    (net (code "26") (name "LVDS_ADC_MISO+") (class "Default")
      (node (ref "DD4mc") (pin "3") (pinfunction "RIN+_3") (pintype "passive"))
      (node (ref "R18mc") (pin "1") (pinfunction "1_1") (pintype "passive"))
      (node (ref "VD14mc") (pin "2") (pinfunction "2_2") (pintype "passive"))
    )
    (net (code "27") (name "LVDS_ADC_MISO-") (class "Default")
      (node (ref "DD4mc") (pin "4") (pinfunction "RIN-_4") (pintype "passive"))
      (node (ref "R18mc") (pin "2") (pinfunction "2_2") (pintype "passive"))
      (node (ref "VD15mc") (pin "2") (pinfunction "2_2") (pintype "passive"))
      (node (ref "X3mc") (pin "1") (pinfunction "1_1") (pintype "passive"))
    )
    (net (code "28") (name "LVDS_ADC_MOSI+") (class "Default")
      (node (ref "DD3mc") (pin "11") (pinfunction "DOUT3+_11") (pintype "passive"))
      (node (ref "VD16mc") (pin "3") (pinfunction "3_3") (pintype "passive"))
      (node (ref "X2mc") (pin "5") (pinfunction "5_5") (pintype "passive"))
    )
    (net (code "29") (name "LVDS_ADC_MOSI-") (class "Default")
      (node (ref "DD3mc") (pin "12") (pinfunction "DOUT3-_12") (pintype "passive"))
      (node (ref "VD16mc") (pin "1") (pinfunction "1_1") (pintype "passive"))
      (node (ref "X2mc") (pin "6") (pinfunction "6_6") (pintype "passive"))
      (node (ref "X3mc") (pin "2") (pinfunction "2_2") (pintype "passive"))
    )
    (net (code "30") (name "LVDS_ADC_SCK+") (class "Default")
      (node (ref "DD3mc") (pin "14") (pinfunction "DOUT2+_14") (pintype "passive"))
      (node (ref "VD16mc") (pin "5") (pinfunction "5_5") (pintype "passive"))
      (node (ref "X2mc") (pin "3") (pinfunction "3_3") (pintype "passive"))
    )
    (net (code "31") (name "LVDS_ADC_SCK-") (class "Default")
      (node (ref "DD3mc") (pin "13") (pinfunction "DOUT2-_13") (pintype "passive"))
      (node (ref "VD16mc") (pin "4") (pinfunction "4_4") (pintype "passive"))
      (node (ref "X2mc") (pin "4") (pinfunction "4_4") (pintype "passive"))
    )
    (net (code "32") (name "LoRa_UART2_RX") (class "Default")
      (node (ref "DD1mc") (pin "68") (pinfunction "PA9_68") (pintype "passive"))
    )
    (net (code "33") (name "LoRa_UART2_TX") (class "Default")
      (node (ref "DD1mc") (pin "69") (pinfunction "PA10_69") (pintype "passive"))
    )
    (net (code "34") (name "MK_GSM_RX") (class "Default")
      (node (ref "DD1mc") (pin "48") (pinfunction "PB11_48") (pintype "passive"))
    )
    (net (code "35") (name "MK_GSM_TX") (class "Default")
      (node (ref "DD1mc") (pin "47") (pinfunction "PB10_47") (pintype "passive"))
    )
    (net (code "36") (name "MK_LVDS_CS") (class "Default")
      (node (ref "DD1mc") (pin "29") (pinfunction "PA4_29") (pintype "passive"))
      (node (ref "DD3mc") (pin "2") (pinfunction "DIN1_2") (pintype "passive"))
    )
    (net (code "37") (name "MK_LVDS_MISO") (class "Default")
      (node (ref "DD1mc") (pin "31") (pinfunction "PA6_31") (pintype "passive"))
      (node (ref "DD4mc") (pin "5") (pinfunction "ROUT_5") (pintype "passive"))
    )
    (net (code "38") (name "MK_LVDS_MOSI") (class "Default")
      (node (ref "DD1mc") (pin "32") (pinfunction "PA7_32") (pintype "passive"))
      (node (ref "DD3mc") (pin "6") (pinfunction "DIN3_6") (pintype "passive"))
    )
    (net (code "39") (name "MK_LVDS_SCK") (class "Default")
      (node (ref "DD1mc") (pin "30") (pinfunction "PA5_30") (pintype "passive"))
      (node (ref "DD3mc") (pin "3") (pinfunction "DIN2_3") (pintype "passive"))
    )
    (net (code "40") (name "MK_To_RFID_EN") (class "Default")
      (node (ref "DD1mc") (pin "67") (pinfunction "PA8_67") (pintype "passive"))
    )
    (net (code "41") (name "MK_To_RFID_GPI") (class "Default")
      (node (ref "DD1mc") (pin "61") (pinfunction "PD14_61") (pintype "passive"))
    )
    (net (code "42") (name "MK_To_RFID_GPO") (class "Default")
      (node (ref "DD1mc") (pin "62") (pinfunction "PD15_62") (pintype "passive"))
    )
    (net (code "43") (name "MK_to_RFID_RX") (class "Default")
      (node (ref "DD1mc") (pin "64") (pinfunction "PC7_64") (pintype "passive"))
    )
    (net (code "44") (name "MK_to_RFID_TX") (class "Default")
      (node (ref "DD1mc") (pin "63") (pinfunction "PC6_63") (pintype "passive"))
    )
    (net (code "45") (name "NRST") (class "Default")
      (node (ref "C2mc") (pin "1") (pinfunction "1_1") (pintype "passive"))
      (node (ref "DD1mc") (pin "14") (pinfunction "NRST_14") (pintype "passive"))
      (node (ref "X1mc") (pin "1") (pinfunction "1_1") (pintype "passive"))
    )
    (net (code "46") (name "NRST_LoRa") (class "Default")
      (node (ref "DD1mc") (pin "84") (pinfunction "PD3_84") (pintype "passive"))
    )
    (net (code "47") (name "Net-(DD1mcA-BOOT0)") (class "Default")
      (node (ref "DD1mc") (pin "94") (pinfunction "BOOT0_94") (pintype "passive"))
      (node (ref "R4mc") (pin "2") (pinfunction "2_2") (pintype "passive"))
    )
    (net (code "48") (name "Net-(DD1mcA-PD12)") (class "Default")
      (node (ref "DD1mc") (pin "59") (pinfunction "PD12_59") (pintype "passive"))
      (node (ref "R16mc") (pin "2") (pinfunction "2_2") (pintype "passive"))
    )
    (net (code "49") (name "Net-(DD1mcB-OSC_IN)") (class "Default")
      (node (ref "C6mc") (pin "2") (pinfunction "2_2") (pintype "passive"))
      (node (ref "DD1mc") (pin "12") (pinfunction "OSC_IN_12") (pintype "passive"))
      (node (ref "ZQ1mc") (pin "2") (pinfunction "2_2") (pintype "passive"))
    )
    (net (code "50") (name "Net-(DD1mcB-OSC_OUT)") (class "Default")
      (node (ref "C9mc") (pin "2") (pinfunction "2_2") (pintype "passive"))
      (node (ref "DD1mc") (pin "13") (pinfunction "OSC_OUT_13") (pintype "passive"))
      (node (ref "ZQ1mc") (pin "1") (pinfunction "1_1") (pintype "passive"))
    )
    (net (code "51") (name "Net-(DD1mcB-VCAP_1)") (class "Default")
      (node (ref "C7mc") (pin "1") (pinfunction "1_1") (pintype "passive"))
      (node (ref "DD1mc") (pin "49") (pinfunction "VCAP_1_49") (pintype "passive"))
    )
    (net (code "52") (name "Net-(DD1mcB-VCAP_2)") (class "Default")
      (node (ref "C8mc") (pin "1") (pinfunction "1_1") (pintype "passive"))
      (node (ref "DD1mc") (pin "73") (pinfunction "VCAP_2_73") (pintype "passive"))
    )
    (net (code "53") (name "Net-(R5mc-Pad1)") (class "Default")
      (node (ref "R5mc") (pin "1") (pinfunction "1_1") (pintype "passive"))
      (node (ref "VD1mc") (pin "1") (pinfunction "1_1") (pintype "passive"))
    )
    (net (code "54") (name "Net-(R6mc-Pad1)") (class "Default")
      (node (ref "R6mc") (pin "1") (pinfunction "1_1") (pintype "passive"))
      (node (ref "VD2mc") (pin "1") (pinfunction "1_1") (pintype "passive"))
    )
    (net (code "55") (name "Net-(R7mc-Pad1)") (class "Default")
      (node (ref "R7mc") (pin "1") (pinfunction "1_1") (pintype "passive"))
      (node (ref "VD3mc") (pin "1") (pinfunction "1_1") (pintype "passive"))
    )
    (net (code "56") (name "Net-(R8mc-Pad1)") (class "Default")
      (node (ref "R8mc") (pin "1") (pinfunction "1_1") (pintype "passive"))
      (node (ref "VD4mc") (pin "1") (pinfunction "1_1") (pintype "passive"))
    )
    (net (code "57") (name "Net-(R9mc-Pad1)") (class "Default")
      (node (ref "R9mc") (pin "1") (pinfunction "1_1") (pintype "passive"))
      (node (ref "VD5mc") (pin "1") (pinfunction "1_1") (pintype "passive"))
    )
    (net (code "58") (name "Net-(R10mc-Pad1)") (class "Default")
      (node (ref "R10mc") (pin "1") (pinfunction "1_1") (pintype "passive"))
      (node (ref "VD6mc") (pin "1") (pinfunction "1_1") (pintype "passive"))
    )
    (net (code "59") (name "Net-(R11mc-Pad1)") (class "Default")
      (node (ref "R11mc") (pin "1") (pinfunction "1_1") (pintype "passive"))
      (node (ref "VD7mc") (pin "1") (pinfunction "1_1") (pintype "passive"))
    )
    (net (code "60") (name "Net-(R12mc-Pad1)") (class "Default")
      (node (ref "R12mc") (pin "1") (pinfunction "1_1") (pintype "passive"))
      (node (ref "VD8mc") (pin "1") (pinfunction "1_1") (pintype "passive"))
    )
    (net (code "61") (name "Net-(R13mc-Pad1)") (class "Default")
      (node (ref "R13mc") (pin "1") (pinfunction "1_1") (pintype "passive"))
      (node (ref "VD9mc") (pin "1") (pinfunction "1_1") (pintype "passive"))
    )
    (net (code "62") (name "Net-(R14mc-Pad1)") (class "Default")
      (node (ref "R14mc") (pin "1") (pinfunction "1_1") (pintype "passive"))
      (node (ref "VD10mc") (pin "1") (pinfunction "1_1") (pintype "passive"))
    )
    (net (code "63") (name "Net-(R15mc-Pad1)") (class "Default")
      (node (ref "R15mc") (pin "1") (pinfunction "1_1") (pintype "passive"))
      (node (ref "VD11mc") (pin "1") (pinfunction "1_1") (pintype "passive"))
    )
    (net (code "64") (name "Net-(R16mc-Pad1)") (class "Default")
      (node (ref "R16mc") (pin "1") (pinfunction "1_1") (pintype "passive"))
      (node (ref "VD12mc") (pin "1") (pinfunction "1_1") (pintype "passive"))
    )
    (net (code "65") (name "Net-(R17mc-Pad1)") (class "Default")
      (node (ref "R17mc") (pin "1") (pinfunction "1_1") (pintype "passive"))
      (node (ref "VD13mc") (pin "1") (pinfunction "1_1") (pintype "passive"))
    )
    (net (code "66") (name "PE") (class "Default")
      (node (ref "X3mc") (pin "5") (pinfunction "5_5") (pintype "passive"))
    )
    (net (code "67") (name "RFID_HEAT") (class "Default")
      (node (ref "DD1mc") (pin "60") (pinfunction "PD13_60") (pintype "passive"))
    )
    (net (code "68") (name "RFID_LINK") (class "Default")
      (node (ref "DD1mc") (pin "46") (pinfunction "PE15_46") (pintype "passive"))
      (node (ref "R14mc") (pin "2") (pinfunction "2_2") (pintype "passive"))
    )
    (net (code "69") (name "SDIO_CLK") (class "Default")
      (node (ref "DD1mc") (pin "80") (pinfunction "PC12_80") (pintype "passive"))
      (node (ref "R22mc") (pin "2") (pinfunction "2_2") (pintype "passive"))
      (node (ref "VD19mc") (pin "5") (pinfunction "5_5") (pintype "passive"))
      (node (ref "X4mc") (pin "5") (pinfunction "CLK_5") (pintype "passive"))
    )
    (net (code "70") (name "SDIO_CMD") (class "Default")
      (node (ref "DD1mc") (pin "83") (pinfunction "PD2_83") (pintype "passive"))
      (node (ref "R21mc") (pin "2") (pinfunction "2_2") (pintype "passive"))
      (node (ref "VD19mc") (pin "4") (pinfunction "4_4") (pintype "passive"))
      (node (ref "X4mc") (pin "3") (pinfunction "C/R_3") (pintype "passive"))
    )
    (net (code "71") (name "SDIO_D0") (class "Default")
      (node (ref "DD1mc") (pin "65") (pinfunction "PC8_65") (pintype "passive"))
      (node (ref "R23mc") (pin "2") (pinfunction "2_2") (pintype "passive"))
      (node (ref "VD19mc") (pin "6") (pinfunction "6_6") (pintype "passive"))
      (node (ref "X4mc") (pin "7") (pinfunction "DAT0_7") (pintype "passive"))
    )
    (net (code "72") (name "SDIO_D1") (class "Default")
      (node (ref "DD1mc") (pin "66") (pinfunction "PC9_66") (pintype "passive"))
      (node (ref "R24mc") (pin "2") (pinfunction "2_2") (pintype "passive"))
      (node (ref "VD19mc") (pin "7") (pinfunction "7_7") (pintype "passive"))
      (node (ref "X4mc") (pin "8") (pinfunction "DAT1_8") (pintype "passive"))
    )
    (net (code "73") (name "SDIO_D2") (class "Default")
      (node (ref "DD1mc") (pin "78") (pinfunction "PC10_78") (pintype "passive"))
      (node (ref "R19mc") (pin "1") (pinfunction "1_1") (pintype "passive"))
      (node (ref "VD19mc") (pin "1") (pinfunction "1_1") (pintype "passive"))
      (node (ref "X4mc") (pin "1") (pinfunction "DAT2_1") (pintype "passive"))
    )
    (net (code "74") (name "SDIO_D3") (class "Default")
      (node (ref "DD1mc") (pin "79") (pinfunction "PC11_79") (pintype "passive"))
      (node (ref "R20mc") (pin "2") (pinfunction "2_2") (pintype "passive"))
      (node (ref "VD19mc") (pin "3") (pinfunction "3_3") (pintype "passive"))
      (node (ref "X4mc") (pin "2") (pinfunction "DAT3_2") (pintype "passive"))
    )
    (net (code "75") (name "SDIO_DET") (class "Default")
      (node (ref "R25mc") (pin "2") (pinfunction "2_2") (pintype "passive"))
      (node (ref "VD17mc") (pin "2") (pinfunction "2_2") (pintype "passive"))
      (node (ref "X4mc") (pin "9") (pinfunction "CD_SW1_9") (pintype "passive"))
    )
    (net (code "76") (name "SWCLK") (class "Default")
      (node (ref "DD1mc") (pin "76") (pinfunction "SWCLK_76") (pintype "passive"))
      (node (ref "X1mc") (pin "6") (pinfunction "6_6") (pintype "passive"))
    )
    (net (code "77") (name "SWDIO") (class "Default")
      (node (ref "DD1mc") (pin "72") (pinfunction "SWDIO_72") (pintype "passive"))
      (node (ref "X1mc") (pin "8") (pinfunction "8_8") (pintype "passive"))
    )
    (net (code "78") (name "SWO") (class "Default")
      (node (ref "DD1mc") (pin "89") (pinfunction "SWO_89") (pintype "passive"))
      (node (ref "X1mc") (pin "3") (pinfunction "3_3") (pintype "passive"))
    )
    (net (code "79") (name "TS1_ALERT") (class "Default")
      (node (ref "DD1mc") (pin "91") (pinfunction "PB5_91") (pintype "passive"))
    )
    (net (code "80") (name "TS2_ALERT") (class "Default")
      (node (ref "DD1mc") (pin "92") (pinfunction "PB6_92") (pintype "passive"))
      (node (ref "DD2mc") (pin "3") (pinfunction "ALERT_3") (pintype "passive"))
      (node (ref "R1mc") (pin "1") (pinfunction "1_1") (pintype "passive"))
      (node (ref "X5mc") (pin "3") (pinfunction "3_3") (pintype "passive"))
    )
    (net (code "81") (name "TS_SCL") (class "Default")
      (node (ref "DD1mc") (pin "95") (pinfunction "PB8_95") (pintype "passive"))
      (node (ref "DD2mc") (pin "1") (pinfunction "SCL_1") (pintype "passive"))
      (node (ref "R2mc") (pin "1") (pinfunction "1_1") (pintype "passive"))
      (node (ref "X5mc") (pin "2") (pinfunction "2_2") (pintype "passive"))
    )
    (net (code "82") (name "TS_SDA") (class "Default")
      (node (ref "DD1mc") (pin "93") (pinfunction "PB7_93") (pintype "passive"))
      (node (ref "DD2mc") (pin "6") (pinfunction "SDA_6") (pintype "passive"))
      (node (ref "R3mc") (pin "1") (pinfunction "1_1") (pintype "passive"))
      (node (ref "X5mc") (pin "1") (pinfunction "1_1") (pintype "passive"))
    )
    (net (code "83") (name "unconnected-(DD1mcA-BOOT1-Pad37)") (class "Default")
      (node (ref "DD1mc") (pin "37") (pinfunction "BOOT1_37") (pintype "passive+no_connect"))
    )
    (net (code "84") (name "unconnected-(DD1mcA-JTDI-Pad77)") (class "Default")
      (node (ref "DD1mc") (pin "77") (pinfunction "JTDI_77") (pintype "passive"))
    )
    (net (code "85") (name "unconnected-(DD1mcA-NJTRST-Pad90)") (class "Default")
      (node (ref "DD1mc") (pin "90") (pinfunction "NJTRST_90") (pintype "passive+no_connect"))
    )
    (net (code "86") (name "unconnected-(DD1mcA-PA3-Pad26)") (class "Default")
      (node (ref "DD1mc") (pin "26") (pinfunction "PA3_26") (pintype "passive"))
    )
    (net (code "87") (name "unconnected-(DD1mcA-PA11-Pad70)") (class "Default")
      (node (ref "DD1mc") (pin "70") (pinfunction "PA11_70") (pintype "passive"))
    )
    (net (code "88") (name "unconnected-(DD1mcA-PA12-Pad71)") (class "Default")
      (node (ref "DD1mc") (pin "71") (pinfunction "PA12_71") (pintype "passive"))
    )
    (net (code "89") (name "unconnected-(DD1mcA-PB0-Pad35)") (class "Default")
      (node (ref "DD1mc") (pin "35") (pinfunction "PB0_35") (pintype "passive"))
    )
    (net (code "90") (name "unconnected-(DD1mcA-PB1-Pad36)") (class "Default")
      (node (ref "DD1mc") (pin "36") (pinfunction "PB1_36") (pintype "passive"))
    )
    (net (code "91") (name "unconnected-(DD1mcA-PB9-Pad96)") (class "Default")
      (node (ref "DD1mc") (pin "96") (pinfunction "PB9_96") (pintype "passive"))
    )
    (net (code "92") (name "unconnected-(DD1mcA-PB12-Pad51)") (class "Default")
      (node (ref "DD1mc") (pin "51") (pinfunction "PB12_51") (pintype "passive"))
    )
    (net (code "93") (name "unconnected-(DD1mcA-PB13-Pad52)") (class "Default")
      (node (ref "DD1mc") (pin "52") (pinfunction "PB13_52") (pintype "passive"))
    )
    (net (code "94") (name "unconnected-(DD1mcA-PB14-Pad53)") (class "Default")
      (node (ref "DD1mc") (pin "53") (pinfunction "PB14_53") (pintype "passive"))
    )
    (net (code "95") (name "unconnected-(DD1mcA-PB15-Pad54)") (class "Default")
      (node (ref "DD1mc") (pin "54") (pinfunction "PB15_54") (pintype "passive"))
    )
    (net (code "96") (name "unconnected-(DD1mcA-PC0-Pad15)") (class "Default")
      (node (ref "DD1mc") (pin "15") (pinfunction "PC0_15") (pintype "passive"))
    )
    (net (code "97") (name "unconnected-(DD1mcA-PC1-Pad16)") (class "Default")
      (node (ref "DD1mc") (pin "16") (pinfunction "PC1_16") (pintype "passive"))
    )
    (net (code "98") (name "unconnected-(DD1mcA-PC2-Pad17)") (class "Default")
      (node (ref "DD1mc") (pin "17") (pinfunction "PC2_17") (pintype "passive"))
    )
    (net (code "99") (name "unconnected-(DD1mcA-PC3-Pad18)") (class "Default")
      (node (ref "DD1mc") (pin "18") (pinfunction "PC3_18") (pintype "passive"))
    )
    (net (code "100") (name "unconnected-(DD1mcA-PC4-Pad33)") (class "Default")
      (node (ref "DD1mc") (pin "33") (pinfunction "PC4_33") (pintype "passive"))
    )
    (net (code "101") (name "unconnected-(DD1mcA-PC5-Pad34)") (class "Default")
      (node (ref "DD1mc") (pin "34") (pinfunction "PC5_34") (pintype "passive"))
    )
    (net (code "102") (name "unconnected-(DD1mcA-PC13-Pad7)") (class "Default")
      (node (ref "DD1mc") (pin "7") (pinfunction "PC13_7") (pintype "passive"))
    )
    (net (code "103") (name "unconnected-(DD1mcA-PD0-Pad81)") (class "Default")
      (node (ref "DD1mc") (pin "81") (pinfunction "PD0_81") (pintype "passive"))
    )
    (net (code "104") (name "unconnected-(DD1mcA-PD1-Pad82)") (class "Default")
      (node (ref "DD1mc") (pin "82") (pinfunction "PD1_82") (pintype "passive"))
    )
    (net (code "105") (name "unconnected-(DD1mcA-PD5-Pad86)") (class "Default")
      (node (ref "DD1mc") (pin "86") (pinfunction "PD5_86") (pintype "passive"))
    )
    (net (code "106") (name "unconnected-(DD1mcA-PD6-Pad87)") (class "Default")
      (node (ref "DD1mc") (pin "87") (pinfunction "PD6_87") (pintype "passive"))
    )
    (net (code "107") (name "unconnected-(DD1mcA-PD7-Pad88)") (class "Default")
      (node (ref "DD1mc") (pin "88") (pinfunction "PD7_88") (pintype "passive"))
    )
    (net (code "108") (name "unconnected-(DD1mcA-PD8-Pad55)") (class "Default")
      (node (ref "DD1mc") (pin "55") (pinfunction "PD8_55") (pintype "passive"))
    )
    (net (code "109") (name "unconnected-(DD1mcA-PE6-Pad5)") (class "Default")
      (node (ref "DD1mc") (pin "5") (pinfunction "PE6_5") (pintype "passive"))
    )
    (net (code "110") (name "unconnected-(DD1mcA-PE7-Pad38)") (class "Default")
      (node (ref "DD1mc") (pin "38") (pinfunction "PE7_38") (pintype "passive"))
    )
    (net (code "111") (name "unconnected-(DD1mcB-OSC32_IN-Pad8)") (class "Default")
      (node (ref "DD1mc") (pin "8") (pinfunction "OSC32_IN_8") (pintype "passive+no_connect"))
    )
    (net (code "112") (name "unconnected-(DD1mcB-OSC32_OUT-Pad9)") (class "Default")
      (node (ref "DD1mc") (pin "9") (pinfunction "OSC32_OUT_9") (pintype "passive+no_connect"))
    )
    (net (code "113") (name "unconnected-(DD3mc-DIN4-Pad7)") (class "Default")
      (node (ref "DD3mc") (pin "7") (pinfunction "DIN4_7") (pintype "passive+no_connect"))
    )
    (net (code "114") (name "unconnected-(DD3mc-DOUT4+-Pad10)") (class "Default")
      (node (ref "DD3mc") (pin "10") (pinfunction "DOUT4+_10") (pintype "passive+no_connect"))
    )
    (net (code "115") (name "unconnected-(DD3mc-DOUT4--Pad9)") (class "Default")
      (node (ref "DD3mc") (pin "9") (pinfunction "DOUT4-_9") (pintype "passive+no_connect"))
    )
    (net (code "116") (name "unconnected-(X4mc-CD_SW2-Pad10)") (class "Default")
      (node (ref "X4mc") (pin "10") (pinfunction "CD_SW2_10") (pintype "passive+no_connect"))
    )
  )
)
